# Input.net
KiCad netlist of a schematic drawn in Altium Designer
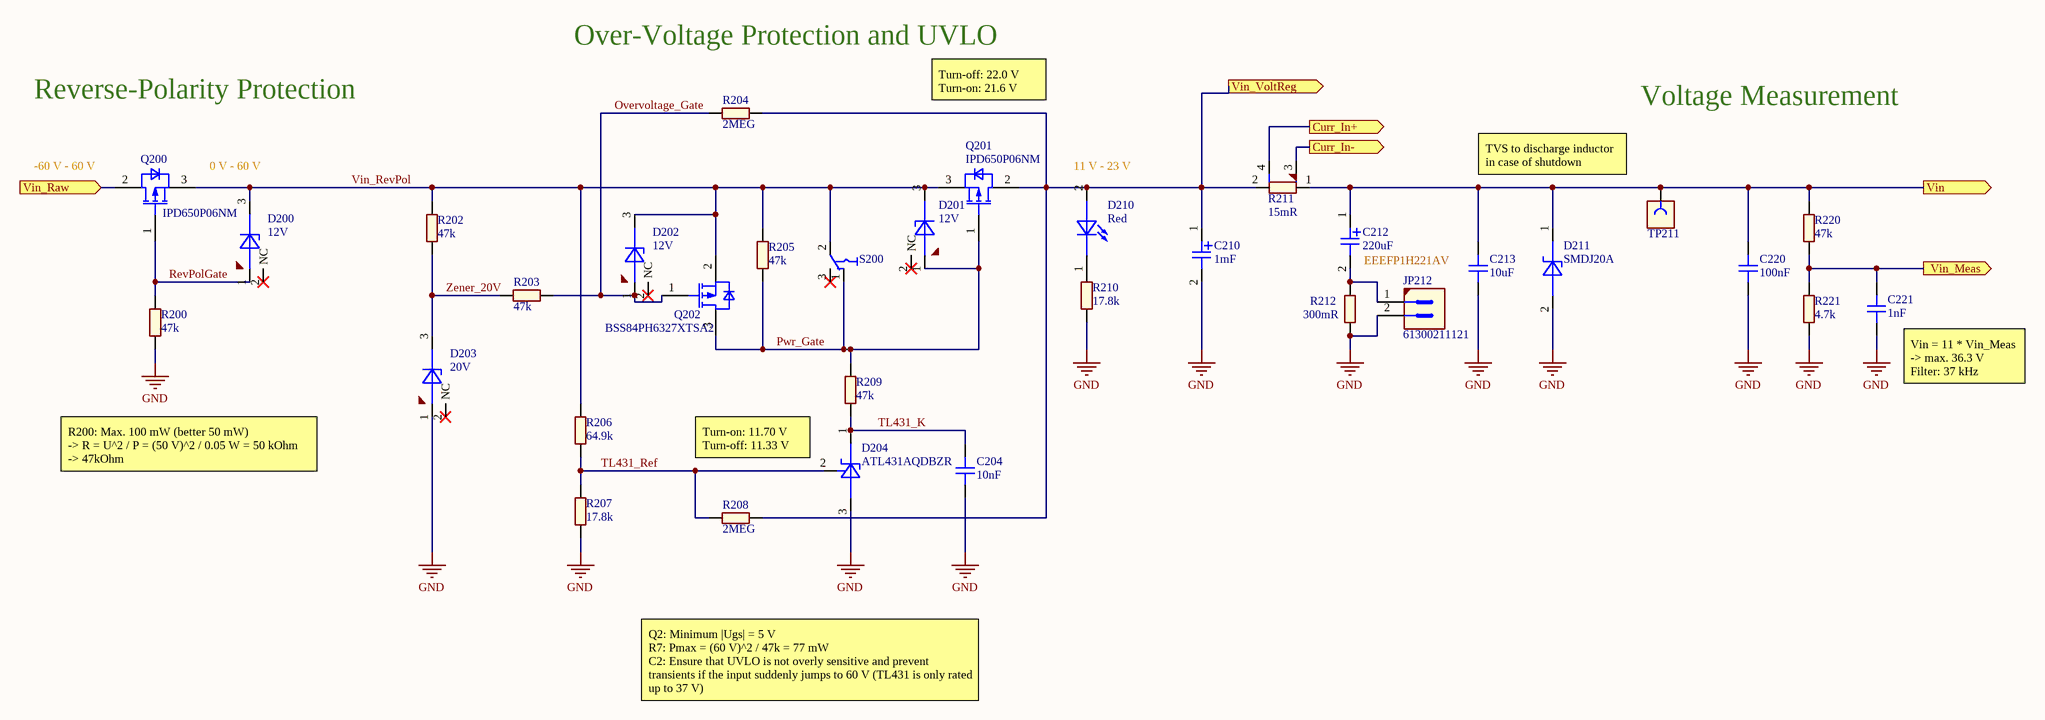
[diagram p0: Input.SchDoc]

(export (version "E")
  (design (tool "Eeschema 10.0.6"))
  (components
    (comp (ref "C204")
      (value "10nF")
      (footprint "CAPC1608X90N-4")
      (description "CAP / CERA / 10nF / 50V / 10% / X8R (EIA) / -55°C to 150°C / 0603(1608) / SMD / -")
      (fields
        (field (name "LEGACY PARTNUMBER") "CAP01010834")
        (field (name "MANUFACTURER") "TDK Corporation")
      )
      (libsource (lib "PCBLibraryData") (part "CAP-SGL-STD-02P_00000001"))
    )
    (comp (ref "C210")
      (value "1mF")
      (footprint "CAPPRD500W60D1300H2700B")
      (fields (field (name "MANUFACTURER") "Kemet"))
      (libsource (lib "PCBLibraryData") (part "CAP-SGL-POL-02P_00000002"))
    )
    (comp (ref "C212")
      (value "220uF")
      (footprint "CAPAE1030X1050N-2")
      (fields (field (name "MANUFACTURER") "Wurth Elektronik"))
      (libsource (lib "PCBLibraryData") (part "CAP-SGL-POL-02P_00000002"))
    )
    (comp (ref "C213")
      (value "10uF")
      (footprint "CAPC3216X190N-1")
      (description "CAP / CERA / 10uF / 50V / 20% / X5R (EIA) / -55°C to 85°C / 1206 (3216) / SMD / -")
      (fields (field (name "MANUFACTURER") "Taiyo Yuden"))
      (libsource (lib "PCBLibraryData") (part "CAP-SGL-STD-02P_00000001"))
    )
    (comp (ref "C220")
      (value "100nF")
      (footprint "CAPC1608X90N-2")
      (description "CAP / CERA / 100nF / 50V / 10% / X7R (EIA) / -55°C to 125°C / 0603 / SMD / -")
      (fields (field (name "MANUFACTURER") "AVX"))
      (libsource (lib "PCBLibraryData") (part "CAP-SGL-STD-02P_00000001"))
    )
    (comp (ref "C221")
      (value "1nF")
      (footprint "CAPC1608X87N-1")
      (description "CAP / CERA / 1nF / 50V / 10% / X7R (EIA) / -55°C to 125°C / 0603 (1608) / SMD / -")
      (fields (field (name "MANUFACTURER") "Wurth Elektronik"))
      (libsource (lib "PCBLibraryData") (part "CAP-SGL-STD-02P_00000001"))
    )
    (comp (ref "D200")
      (value "12V")
      (footprint "SOT95P230X110-3N")
      (description "Voltage regulator diodes")
      (fields (field (name "MANUFACTURER") "Nexperia"))
      (libsource (lib "PCBLibraryData") (part "d_zener_a1c3_3p"))
    )
    (comp (ref "D201")
      (value "12V")
      (footprint "SOT95P230X110-3N")
      (description "Voltage regulator diodes")
      (fields (field (name "MANUFACTURER") "Nexperia"))
      (libsource (lib "PCBLibraryData") (part "d_zener_a1c3_3p"))
    )
    (comp (ref "D202")
      (value "12V")
      (footprint "SOT95P230X110-3N")
      (description "Voltage regulator diodes")
      (fields (field (name "MANUFACTURER") "Nexperia"))
      (libsource (lib "PCBLibraryData") (part "d_zener_a1c3_3p"))
    )
    (comp (ref "D203")
      (value "20V")
      (footprint "SOT95P230X110-3N")
      (description "Voltage regulator diodes")
      (fields (field (name "MANUFACTURER") "Nexperia"))
      (libsource (lib "PCBLibraryData") (part "d_zener_a1c3_3p"))
    )
    (comp (ref "D204")
      (value "ATL431AQDBZR")
      (footprint "SOT95P237X112-3N-1")
      (description "ATL431 Adjustable Precision Shunt Regulator")
      (fields (field (name "MANUFACTURER") "Texas Instruments"))
      (libsource (lib "PCBLibraryData") (part "d_tvs_c1a3_3p"))
    )
    (comp (ref "D210")
      (value "Red")
      (footprint "LEDSC160X80X80-2N-1")
      (description "WL-SMCW SMT Mono-color Chip LED Waterclear, Red,630nm")
      (fields (field (name "MANUFACTURER") "Wurth Elektronik"))
      (libsource (lib "PCBLibraryData") (part "d_led_a"))
    )
    (comp (ref "D211")
      (value "SMDJ20A")
      (footprint "DIOM7959X262N")
      (description "TVS Diode, Low Profile Package, Built in Strain Relief, Glass Passivated Chip Junction")
      (fields (field (name "MANUFACTURER") "Littelfuse"))
      (libsource (lib "PCBLibraryData") (part "d_tvs_a"))
    )
    (comp (ref "JP212")
      (value "61300211121")
      (footprint "CON-M-THT-61300211121")
      (description "Header, 2.54mm Pitch, 2 pin, Vertical, Single Row")
      (fields
        (field (name "LEGACY PARTNUMBER") "CON01500943")
        (field (name "MANUFACTURER") "Wurth Elektronik")
      )
      (libsource (lib "PCBLibraryData") (part "Header 2"))
    )
    (comp (ref "Q200")
      (value "IPD650P06NM")
      (footprint "TO228P998X250-3N-V2")
      (description "OptiMOS Power Transistor, -60 V")
      (fields (field (name "MANUFACTURER") "Infineon Technologies"))
      (libsource (lib "PCBLibraryData") (part "igfet_p_ch_enh_dio_1g2d3s_3p"))
    )
    (comp (ref "Q201")
      (value "IPD650P06NM")
      (footprint "TO228P998X250-3N-V2")
      (description "OptiMOS Power Transistor, -60 V")
      (fields (field (name "MANUFACTURER") "Infineon Technologies"))
      (libsource (lib "PCBLibraryData") (part "igfet_p_ch_enh_dio_1g2d3s_3p"))
    )
    (comp (ref "Q202")
      (value "BSS84PH6327XTSA2")
      (footprint "SOT95P240X110-3N-1")
      (description "SIPMOS P-Channel Enhancement Small-Signal-Transistor")
      (fields
        (field (name "LEGACY PARTNUMBER") "IFX01400461")
        (field (name "MANUFACTURER") "Infineon Technologies")
      )
      (libsource (lib "PCBLibraryData") (part "igfet_p_ch_enh_dio_1g2s3d_3p"))
    )
    (comp (ref "R200")
      (value "47k")
      (footprint "RESC1609X50N")
      (description "RES / STD / 47k / 100mW / 1% / 100ppm/K / -55°C to 155°C / 0603 / SMD / -")
      (fields (field (name "LEGACY PARTNUMBER") "RES01801333") (field (name "MANUFACTURER") "Vishay"))
      (libsource (lib "PCBLibraryData") (part "RES-SGL-STD-02P_00000006"))
    )
    (comp (ref "R202")
      (value "47k")
      (footprint "RESC1609X50N")
      (description "RES / STD / 47k / 100mW / 1% / 100ppm/K / -55°C to 155°C / 0603 / SMD / -")
      (fields (field (name "LEGACY PARTNUMBER") "RES01801333") (field (name "MANUFACTURER") "Vishay"))
      (libsource (lib "PCBLibraryData") (part "RES-SGL-STD-02P_00000006"))
    )
    (comp (ref "R203")
      (value "47k")
      (footprint "RESC1609X50N")
      (description "RES / STD / 47k / 100mW / 1% / 100ppm/K / -55°C to 155°C / 0603 / SMD / -")
      (fields (field (name "LEGACY PARTNUMBER") "RES01801333") (field (name "MANUFACTURER") "Vishay"))
      (libsource (lib "") (part "RES-SGL-STD-02P_00000006_3"))
    )
    (comp (ref "R204")
      (value "2MEG")
      (footprint "RESC1609X50N")
      (description "RES / STD / 2MEG / 100mW / 1% / 100ppm/K / -55°C to 155°C / 0603 / SMD / -")
      (fields (field (name "LEGACY PARTNUMBER") "RES01801517") (field (name "MANUFACTURER") "Vishay"))
      (libsource (lib "") (part "RES-SGL-STD-02P_00000006_1"))
    )
    (comp (ref "R205")
      (value "47k")
      (footprint "RESC1609X50N")
      (description "RES / STD / 47k / 100mW / 1% / 100ppm/K / -55°C to 155°C / 0603 / SMD / -")
      (fields (field (name "LEGACY PARTNUMBER") "RES01801333") (field (name "MANUFACTURER") "Vishay"))
      (libsource (lib "PCBLibraryData") (part "RES-SGL-STD-02P_00000006"))
    )
    (comp (ref "R206")
      (value "64.9k")
      (footprint "RESC1609X50N")
      (description "RES / STD / 64.9k / 100mW / 1% / 100ppm/K / -55°C to 155°C / 0603 / SMD / -")
      (fields (field (name "LEGACY PARTNUMBER") "RES01801350") (field (name "MANUFACTURER") "Vishay"))
      (libsource (lib "PCBLibraryData") (part "RES-SGL-STD-02P_00000006"))
    )
    (comp (ref "R207")
      (value "17.8k")
      (footprint "RESC1609X50N")
      (description "RES / STD / 17.8k / 100mW / 1% / 100ppm/K / -55°C to 155°C / 0603 / SMD / -")
      (fields (field (name "LEGACY PARTNUMBER") "RES01801283") (field (name "MANUFACTURER") "Vishay"))
      (libsource (lib "PCBLibraryData") (part "RES-SGL-STD-02P_00000006"))
    )
    (comp (ref "R208")
      (value "2MEG")
      (footprint "RESC1609X50N")
      (description "RES / STD / 2MEG / 100mW / 1% / 100ppm/K / -55°C to 155°C / 0603 / SMD / -")
      (fields (field (name "LEGACY PARTNUMBER") "RES01801517") (field (name "MANUFACTURER") "Vishay"))
      (libsource (lib "") (part "RES-SGL-STD-02P_00000006_1"))
    )
    (comp (ref "R209")
      (value "47k")
      (footprint "RESC1609X50N")
      (description "RES / STD / 47k / 100mW / 1% / 100ppm/K / -55°C to 155°C / 0603 / SMD / -")
      (fields (field (name "LEGACY PARTNUMBER") "RES01801333") (field (name "MANUFACTURER") "Vishay"))
      (libsource (lib "PCBLibraryData") (part "RES-SGL-STD-02P_00000006"))
    )
    (comp (ref "R210")
      (value "17.8k")
      (footprint "RESC1609X50N")
      (description "RES / STD / 17.8k / 100mW / 1% / 100ppm/K / -55°C to 155°C / 0603 / SMD / -")
      (fields (field (name "LEGACY PARTNUMBER") "RES01801283") (field (name "MANUFACTURER") "Vishay"))
      (libsource (lib "PCBLibraryData") (part "RES-SGL-STD-02P_00000006"))
    )
    (comp (ref "R211")
      (value "15mR")
      (footprint "RES-SMD-L4T12")
      (description "RES / STD / 15mR / 500mW / 1% / 75ppm/K / -55°C to 155°C / 1206 (3216) / SMD / -")
      (fields (field (name "MANUFACTURER") "Ohmite"))
      (libsource (lib "PCBLibraryData") (part "RES-SHT-STD-04P_00097BE5"))
    )
    (comp (ref "R212")
      (value "300mR")
      (footprint "RESC6432X89N-1")
      (description "RES / STD / 300mR / 1W / 1% / 75ppm/K / -65°C to 170°C / 2512 / SMD / -")
      (fields (field (name "MANUFACTURER") "Vishay"))
      (libsource (lib "") (part "RES-SGL-STD-02P_00000006_1"))
    )
    (comp (ref "R220")
      (value "47k")
      (footprint "RESC1609X50N")
      (description "RES / STD / 47k / 100mW / 1% / 100ppm/K / -55°C to 155°C / 0603 / SMD / -")
      (fields (field (name "LEGACY PARTNUMBER") "RES01801333") (field (name "MANUFACTURER") "Vishay"))
      (libsource (lib "") (part "RES-SGL-STD-02P_00000006_2"))
    )
    (comp (ref "R221")
      (value "4.7k")
      (footprint "RESC1609X50N")
      (description "RES / STD / 4.7k / 100mW / 1% / 100ppm/K / -55°C to 155°C / 0603 / SMD / -")
      (fields (field (name "LEGACY PARTNUMBER") "RES01801219") (field (name "MANUFACTURER") "Vishay"))
      (libsource (lib "PCBLibraryData") (part "RES-SGL-STD-02P_00000006"))
    )
    (comp (ref "S200")
      (value "CL-SB-12A-01T")
      (footprint "SW-SMD-CL-SB-12A-01T")
      (description "Slid Switch, 12V, 200mA")
      (fields (field (name "MANUFACTURER") "NIDEC COPAL ELECTRONICS, Inc."))
      (libsource (lib "PCBLibraryData") (part "sw_co213_3p"))
    )
    (comp (ref "TP211")
      (value "S1751-46R")
      (footprint "CON-SMD-TT-S1751-46")
      (description "Test Terminal, Surface Mount (Tape and Reeled Components)")
      (fields (field (name "LEGACY PARTNUMBER") "CON01501015") (field (name "MANUFACTURER") "Harwin"))
      (libsource (lib "PCBLibraryData") (part "connector_1_f"))
    )
  )
  (nets
    (net (code "1") (name "/Curr_In+") (class "Default")
      (node (ref "R211") (pin "4") (pinfunction "I2_4") (pintype "passive"))
    )
    (net (code "2") (name "/Curr_In-") (class "Default")
      (node (ref "R211") (pin "3") (pinfunction "I1_3") (pintype "passive"))
    )
    (net (code "3") (name "/Overvoltage_Gate") (class "Default")
      (node (ref "D202") (pin "1") (pinfunction "ANODE_1") (pintype "passive"))
      (node (ref "Q202") (pin "1") (pinfunction "GATE_1") (pintype "passive"))
      (node (ref "R203") (pin "1") (pinfunction "1_1") (pintype "passive"))
      (node (ref "R204") (pin "1") (pinfunction "1_1") (pintype "passive"))
    )
    (net (code "4") (name "/Pwr_Gate") (class "Default")
      (node (ref "D201") (pin "1") (pinfunction "ANODE_1") (pintype "passive"))
      (node (ref "Q201") (pin "1") (pinfunction "GATE_1") (pintype "passive"))
      (node (ref "Q202") (pin "3") (pinfunction "DRAIN_3") (pintype "passive"))
      (node (ref "R205") (pin "1") (pinfunction "1_1") (pintype "passive"))
      (node (ref "R209") (pin "2") (pinfunction "2_2") (pintype "passive"))
      (node (ref "S200") (pin "1") (pinfunction "1_1") (pintype "passive"))
    )
    (net (code "5") (name "/RevPolGate") (class "Default")
      (node (ref "D200") (pin "1") (pinfunction "ANODE_1") (pintype "passive"))
      (node (ref "Q200") (pin "1") (pinfunction "GATE_1") (pintype "passive"))
      (node (ref "R200") (pin "2") (pinfunction "2_2") (pintype "passive"))
    )
    (net (code "6") (name "/TL431_K") (class "Default")
      (node (ref "C204") (pin "2") (pinfunction "2_2") (pintype "passive"))
      (node (ref "D204") (pin "1") (pinfunction "CATHODE_1") (pintype "passive"))
      (node (ref "R209") (pin "1") (pinfunction "1_1") (pintype "passive"))
    )
    (net (code "7") (name "/TL431_Ref") (class "Default")
      (node (ref "D204") (pin "2") (pinfunction "REF_2") (pintype "passive"))
      (node (ref "R206") (pin "1") (pinfunction "1_1") (pintype "passive"))
      (node (ref "R207") (pin "2") (pinfunction "2_2") (pintype "passive"))
      (node (ref "R208") (pin "1") (pinfunction "1_1") (pintype "passive"))
    )
    (net (code "8") (name "/Vin") (class "Default")
      (node (ref "C212") (pin "1") (pinfunction "1_1") (pintype "passive"))
      (node (ref "C213") (pin "2") (pinfunction "2_2") (pintype "passive"))
      (node (ref "C220") (pin "2") (pinfunction "2_2") (pintype "passive"))
      (node (ref "D211") (pin "1") (pinfunction "CATHODE_1") (pintype "passive"))
      (node (ref "R211") (pin "1") (pinfunction "V1_1") (pintype "passive"))
      (node (ref "R220") (pin "1") (pinfunction "1_1") (pintype "passive"))
      (node (ref "TP211") (pin "1") (pinfunction "1_1") (pintype "passive"))
    )
    (net (code "9") (name "/Vin_Meas") (class "Default")
      (node (ref "C221") (pin "2") (pinfunction "2_2") (pintype "passive"))
      (node (ref "R220") (pin "2") (pinfunction "2_2") (pintype "passive"))
      (node (ref "R221") (pin "2") (pinfunction "2_2") (pintype "passive"))
    )
    (net (code "10") (name "/Vin_Raw") (class "Default")
      (node (ref "Q200") (pin "2") (pinfunction "DRAIN_2") (pintype "passive"))
    )
    (net (code "11") (name "/Vin_RevPol") (class "Default")
      (node (ref "D200") (pin "3") (pinfunction "CATHODE_3") (pintype "passive"))
      (node (ref "D201") (pin "3") (pinfunction "CATHODE_3") (pintype "passive"))
      (node (ref "D202") (pin "3") (pinfunction "CATHODE_3") (pintype "passive"))
      (node (ref "Q200") (pin "3") (pinfunction "SOURCE_3") (pintype "passive"))
      (node (ref "Q201") (pin "3") (pinfunction "SOURCE_3") (pintype "passive"))
      (node (ref "Q202") (pin "2") (pinfunction "SOURCE_2") (pintype "passive"))
      (node (ref "R202") (pin "2") (pinfunction "2_2") (pintype "passive"))
      (node (ref "R205") (pin "2") (pinfunction "2_2") (pintype "passive"))
      (node (ref "R206") (pin "2") (pinfunction "2_2") (pintype "passive"))
      (node (ref "S200") (pin "2") (pinfunction "2_2") (pintype "passive"))
    )
    (net (code "12") (name "/Vin_VoltReg") (class "Default")
      (node (ref "C210") (pin "1") (pinfunction "1_1") (pintype "passive"))
      (node (ref "D210") (pin "2") (pinfunction "Anode_2") (pintype "passive"))
      (node (ref "Q201") (pin "2") (pinfunction "DRAIN_2") (pintype "passive"))
      (node (ref "R204") (pin "2") (pinfunction "2_2") (pintype "passive"))
      (node (ref "R208") (pin "2") (pinfunction "2_2") (pintype "passive"))
      (node (ref "R211") (pin "2") (pinfunction "V2_2") (pintype "passive"))
    )
    (net (code "13") (name "/Zener_20V") (class "Default")
      (node (ref "D203") (pin "3") (pinfunction "CATHODE_3") (pintype "passive"))
      (node (ref "R202") (pin "1") (pinfunction "1_1") (pintype "passive"))
      (node (ref "R203") (pin "2") (pinfunction "2_2") (pintype "passive"))
    )
    (net (code "14") (name "GND") (class "Default")
      (node (ref "C204") (pin "1") (pinfunction "1_1") (pintype "passive"))
      (node (ref "C210") (pin "2") (pinfunction "2_2") (pintype "passive"))
      (node (ref "C213") (pin "1") (pinfunction "1_1") (pintype "passive"))
      (node (ref "C220") (pin "1") (pinfunction "1_1") (pintype "passive"))
      (node (ref "C221") (pin "1") (pinfunction "1_1") (pintype "passive"))
      (node (ref "D203") (pin "1") (pinfunction "ANODE_1") (pintype "passive"))
      (node (ref "D204") (pin "3") (pinfunction "ANODE_3") (pintype "passive"))
      (node (ref "D211") (pin "2") (pinfunction "ANODE_2") (pintype "passive"))
      (node (ref "JP212") (pin "2") (pinfunction "2_2") (pintype "passive"))
      (node (ref "R200") (pin "1") (pinfunction "1_1") (pintype "passive"))
      (node (ref "R207") (pin "1") (pinfunction "1_1") (pintype "passive"))
      (node (ref "R210") (pin "1") (pinfunction "1_1") (pintype "passive"))
      (node (ref "R212") (pin "1") (pinfunction "1_1") (pintype "passive"))
      (node (ref "R221") (pin "1") (pinfunction "1_1") (pintype "passive"))
    )
    (net (code "15") (name "Net-(C212-Pad2)") (class "Default")
      (node (ref "C212") (pin "2") (pinfunction "2_2") (pintype "passive"))
      (node (ref "JP212") (pin "1") (pinfunction "1_1") (pintype "passive"))
      (node (ref "R212") (pin "2") (pinfunction "2_2") (pintype "passive"))
    )
    (net (code "16") (name "Net-(D210-Cathode)") (class "Default")
      (node (ref "D210") (pin "1") (pinfunction "Cathode_1") (pintype "passive"))
      (node (ref "R210") (pin "2") (pinfunction "2_2") (pintype "passive"))
    )
    (net (code "17") (name "unconnected-(D200-NC-Pad2)") (class "Default")
      (node (ref "D200") (pin "2") (pinfunction "NC_2") (pintype "passive+no_connect"))
    )
    (net (code "18") (name "unconnected-(D201-NC-Pad2)") (class "Default")
      (node (ref "D201") (pin "2") (pinfunction "NC_2") (pintype "passive+no_connect"))
    )
    (net (code "19") (name "unconnected-(D202-NC-Pad2)") (class "Default")
      (node (ref "D202") (pin "2") (pinfunction "NC_2") (pintype "passive+no_connect"))
    )
    (net (code "20") (name "unconnected-(D203-NC-Pad2)") (class "Default")
      (node (ref "D203") (pin "2") (pinfunction "NC_2") (pintype "passive+no_connect"))
    )
    (net (code "21") (name "unconnected-(S200-Pad3)") (class "Default")
      (node (ref "S200") (pin "3") (pinfunction "3_3") (pintype "passive+no_connect"))
    )
  )
)
